# Escorna_CPU_2_01.net
KiCad netlist of a schematic drawn in EAGLE
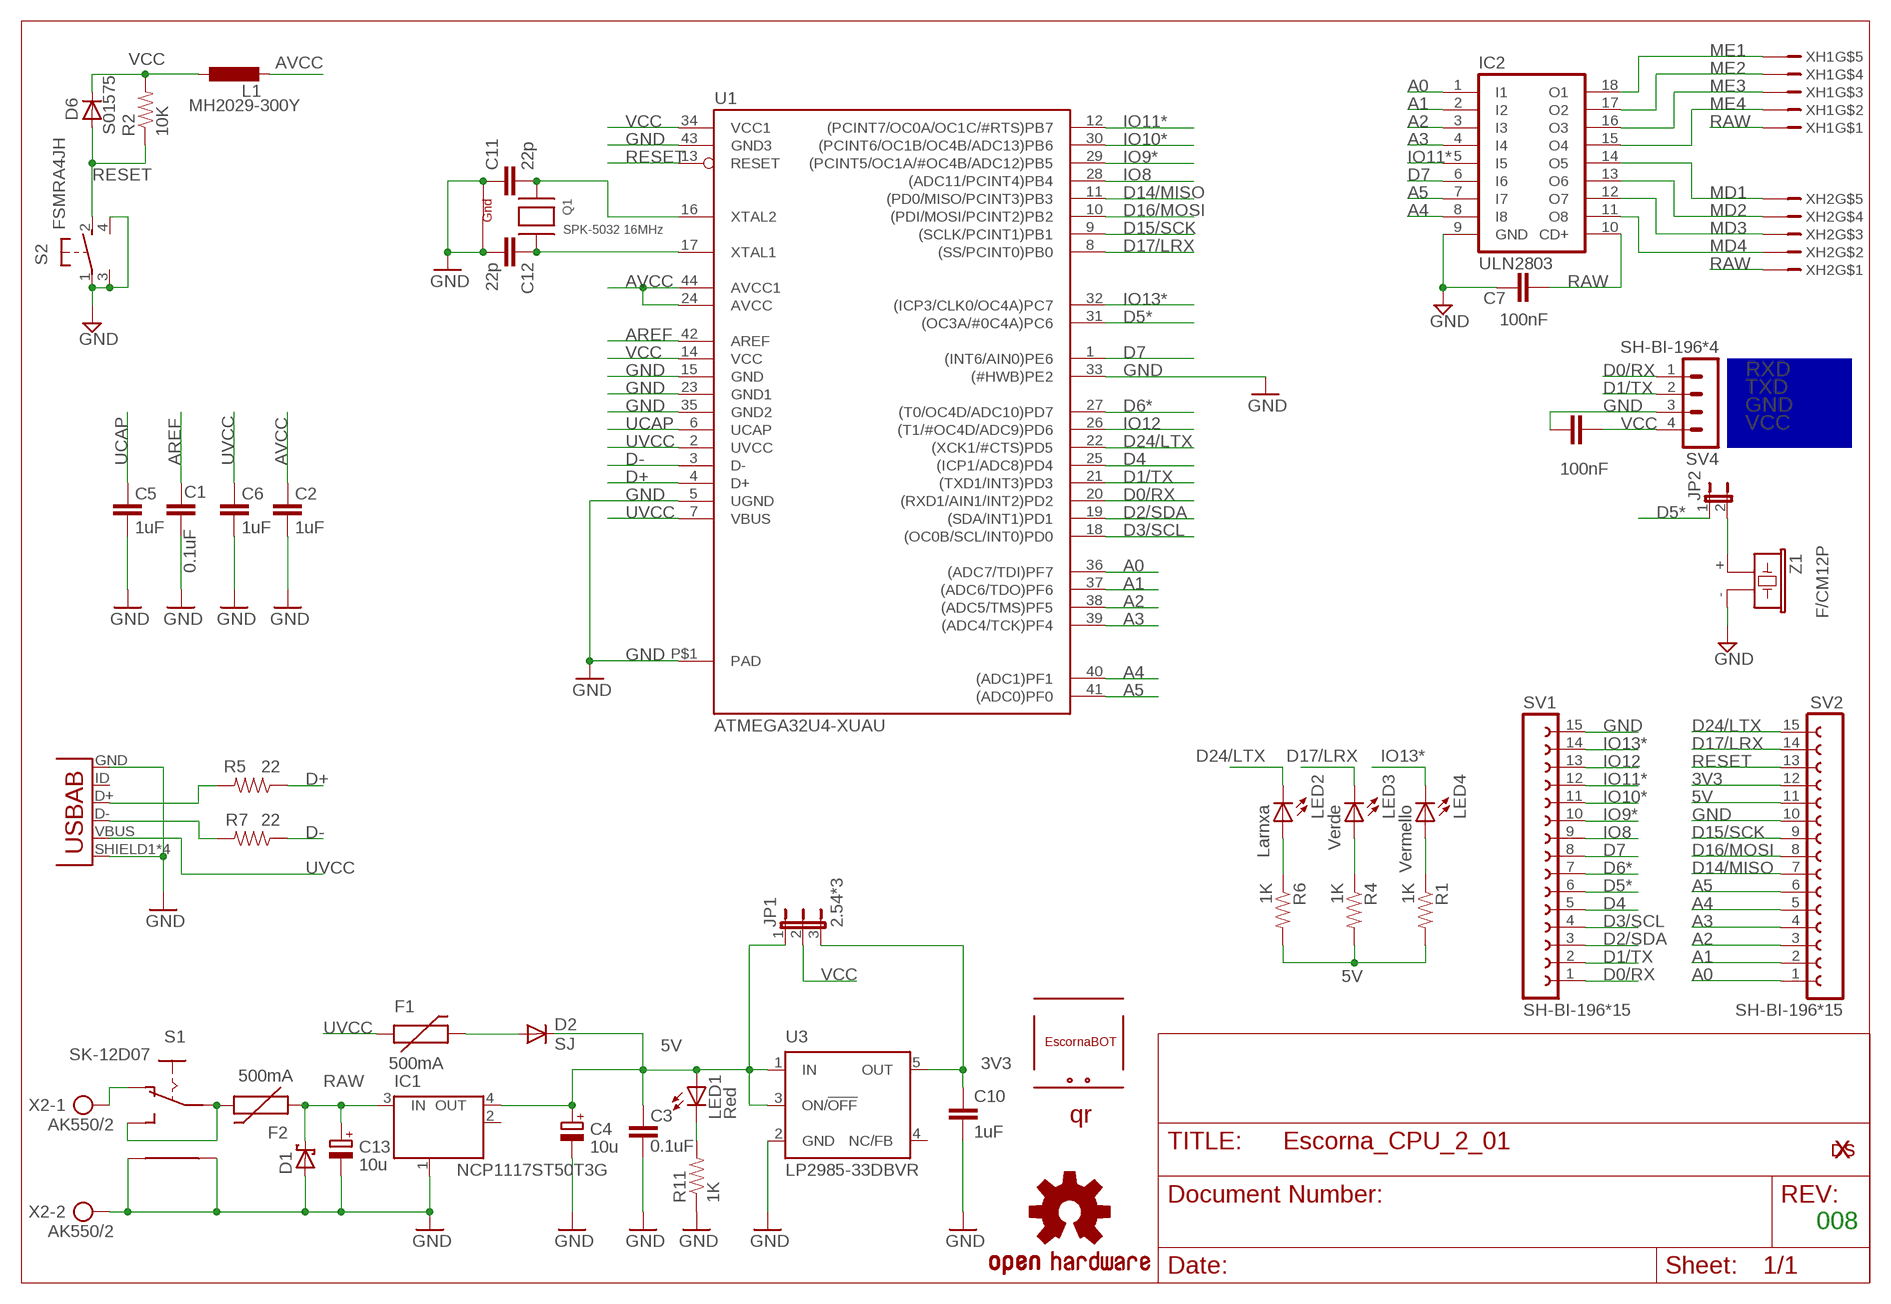
[diagram p0: schematic, sheet 1]

(export (version "E")
  (design (tool "Eeschema 10.0.6"))
  (components
    (comp (ref "C1")
      (value "0.1uF")
      (footprint "eagle-import:0603-CAP")
      (libsource (lib "eagle-import") (part "CAP0603-CAP"))
    )
    (comp (ref "C2")
      (value "1uF")
      (footprint "eagle-import:0603-CAP")
      (libsource (lib "eagle-import") (part "CAP0603-CAP"))
    )
    (comp (ref "C3")
      (value "0.1uF")
      (footprint "eagle-import:0603-CAP")
      (libsource (lib "eagle-import") (part "CAP0603-CAP"))
    )
    (comp (ref "C4")
      (value "10u")
      (footprint "eagle-import:SMC_B")
      (libsource (lib "eagle-import") (part "CPOL-EUSMCB"))
    )
    (comp (ref "C5")
      (value "1uF")
      (footprint "eagle-import:0603-CAP")
      (libsource (lib "eagle-import") (part "CAP0603-CAP"))
    )
    (comp (ref "C6")
      (value "1uF")
      (footprint "eagle-import:0603-CAP")
      (libsource (lib "eagle-import") (part "CAP0603-CAP"))
    )
    (comp (ref "C7")
      (value "100nF")
      (footprint "eagle-import:C0603K")
      (libsource (lib "eagle-import") (part "rcl_C-EUC0603K"))
    )
    (comp (ref "C8")
      (value "100nF")
      (footprint "eagle-import:C0603K")
      (libsource (lib "eagle-import") (part "rcl_C-EUC0603K"))
    )
    (comp (ref "C10")
      (value "1uF")
      (footprint "eagle-import:0603-CAP")
      (libsource (lib "eagle-import") (part "CAP0603-CAP"))
    )
    (comp (ref "C11")
      (value "22p")
      (footprint "eagle-import:C0603-ROUND")
      (libsource (lib "eagle-import") (part "C-EUC0603"))
    )
    (comp (ref "C12")
      (value "22p")
      (footprint "eagle-import:C0603-ROUND")
      (libsource (lib "eagle-import") (part "C-EUC0603"))
    )
    (comp (ref "C13")
      (value "10u")
      (footprint "eagle-import:SMC_B")
      (libsource (lib "eagle-import") (part "CPOL-EUSMCB"))
    )
    (comp (ref "D1")
      (value "SCHOTTKY-DIODESMA")
      (footprint "eagle-import:SMA")
      (libsource (lib "eagle-import") (part "SCHOTTKY-DIODESMA"))
    )
    (comp (ref "D2")
      (value "SJ")
      (footprint "eagle-import:SOD-323")
      (libsource (lib "eagle-import") (part "DIODESOD"))
    )
    (comp (ref "D6")
      (value "S01575")
      (footprint "eagle-import:SOD-323")
      (libsource (lib "eagle-import") (part "DIODESOD"))
    )
    (comp (ref "F1")
      (value "500mA")
      (footprint "eagle-import:PTC-1206")
      (libsource (lib "eagle-import") (part "PTCSMD"))
    )
    (comp (ref "F2")
      (value "500mA")
      (footprint "eagle-import:PTC-1206")
      (libsource (lib "eagle-import") (part "PTCSMD"))
    )
    (comp (ref "IC1")
      (value "NCP1117ST50T3G")
      (footprint "eagle-import:SOT223")
      (libsource (lib "eagle-import") (part "MC33269ST-3.3T3"))
    )
    (comp (ref "IC2")
      (value "ULN2803")
      (footprint "eagle-import:DIL18")
      (libsource (lib "eagle-import") (part "ULN2803A{dblquote}"))
    )
    (comp (ref "JP1")
      (value "2.54*3")
      (footprint "eagle-import:JP2")
      (libsource (lib "eagle-import") (part "JP2E"))
    )
    (comp (ref "JP2")
      (value "JP1E")
      (footprint "eagle-import:JP1")
      (libsource (lib "eagle-import") (part "JP1E"))
    )
    (comp (ref "L1")
      (value "MH2029-300Y")
      (footprint "eagle-import:L2012C")
      (libsource (lib "eagle-import") (part "L-EUL2012C"))
    )
    (comp (ref "LED1")
      (value "Red")
      (footprint "eagle-import:LED-0603")
      (libsource (lib "eagle-import") (part "LED0603"))
    )
    (comp (ref "LED2")
      (value "Larnxa")
      (footprint "eagle-import:LED-0603")
      (libsource (lib "eagle-import") (part "LED0603"))
    )
    (comp (ref "LED3")
      (value "Verde")
      (footprint "eagle-import:LED-0603")
      (libsource (lib "eagle-import") (part "LED0603"))
    )
    (comp (ref "LED4")
      (value "Vermello")
      (footprint "eagle-import:LED-0603")
      (libsource (lib "eagle-import") (part "LED0603"))
    )
    (comp (ref "LOGO1")
      (value "OSHW-LOGOS")
      (footprint "eagle-import:OSHW-LOGO-S")
      (libsource (lib "eagle-import") (part "OSHW-LOGOS"))
    )
    (comp (ref "Q1")
      (value "SPK-5032 16MHz")
      (footprint "eagle-import:NX3225")
      (libsource (lib "eagle-import") (part "XTAL-4-3225"))
    )
    (comp (ref "R1")
      (value "1K")
      (footprint "eagle-import:0603-RES")
      (libsource (lib "eagle-import") (part "RESISTOR0603-RES"))
    )
    (comp (ref "R2")
      (value "10K")
      (footprint "eagle-import:0603-RES")
      (libsource (lib "eagle-import") (part "RESISTOR0603-RES"))
    )
    (comp (ref "R4")
      (value "1K")
      (footprint "eagle-import:0603-RES")
      (libsource (lib "eagle-import") (part "RESISTOR0603-RES"))
    )
    (comp (ref "R5")
      (value "22")
      (footprint "eagle-import:0603-RES")
      (libsource (lib "eagle-import") (part "RESISTOR0603-RES"))
    )
    (comp (ref "R6")
      (value "1K")
      (footprint "eagle-import:0603-RES")
      (libsource (lib "eagle-import") (part "RESISTOR0603-RES"))
    )
    (comp (ref "R7")
      (value "22")
      (footprint "eagle-import:0603-RES")
      (libsource (lib "eagle-import") (part "RESISTOR0603-RES"))
    )
    (comp (ref "R11")
      (value "1K")
      (footprint "eagle-import:0603-RES")
      (libsource (lib "eagle-import") (part "RESISTOR0603-RES"))
    )
    (comp (ref "S1")
      (value "SK-12D07")
      (footprint "eagle-import:SK-12D07")
      (libsource (lib "eagle-import") (part "SK12F14D"))
    )
    (comp (ref "S2")
      (value "FSMRA4JH")
      (footprint "eagle-import:B3F-31XX")
      (fields (field (name "MPN") "B3F-3100"))
      (libsource (lib "eagle-import") (part "31-XX"))
    )
    (comp (ref "SV1")
      (value "SH-BI-196*15")
      (footprint "eagle-import:FE15")
      (libsource (lib "eagle-import") (part "FE15-1"))
    )
    (comp (ref "SV2")
      (value "SH-BI-196*15")
      (footprint "eagle-import:FE15")
      (libsource (lib "eagle-import") (part "FE15-1"))
    )
    (comp (ref "SV4")
      (value "SH-BI-196*4")
      (footprint "eagle-import:MA04-1")
      (libsource (lib "eagle-import") (part "MA04-1"))
    )
    (comp (ref "U$2")
      (value "XDESIG")
      (footprint "eagle-import:XDESIG_CU_2")
      (libsource (lib "eagle-import") (part "XDESIG"))
    )
    (comp (ref "U$3")
      (value "ESCORNABOT")
      (footprint "eagle-import:ESCORNA_PEQUE")
      (libsource (lib "eagle-import") (part "ESCORNABOT"))
    )
    (comp (ref "U$5")
      (value "XDESIG21")
      (footprint "eagle-import:XDESIG")
      (libsource (lib "eagle-import") (part "XDESIG21"))
    )
    (comp (ref "U$6")
      (value "QR25")
      (footprint "eagle-import:ESCORNA_QR25")
      (libsource (lib "eagle-import") (part "QR25"))
    )
    (comp (ref "U1")
      (value "ATMEGA32U4-XUAU")
      (footprint "eagle-import:TQFP44-PAD")
      (libsource (lib "eagle-import") (part "ATMEGA32U4-XUAU"))
    )
    (comp (ref "U2")
      (value "MICRO USB")
      (footprint "eagle-import:USB-AB-MICRO-SMD")
      (libsource (lib "eagle-import") (part "USB-AB"))
    )
    (comp (ref "U3")
      (value "LP2985-33DBVR")
      (footprint "eagle-import:SOT23-DBV")
      (libsource (lib "eagle-import") (part "LP2985-XXDBVR33"))
    )
    (comp (ref "X2")
      (value "AK550/2")
      (footprint "eagle-import:AK550_2")
      (libsource (lib "eagle-import") (part "AK550/2"))
    )
    (comp (ref "XH1")
      (value "XH2.54-5P")
      (footprint "eagle-import:B5B-XH-A")
      (libsource (lib "eagle-import") (part "B5B-XH-A"))
    )
    (comp (ref "XH2")
      (value "XH2.54-5P")
      (footprint "eagle-import:B5B-XH-A")
      (libsource (lib "eagle-import") (part "B5B-XH-A"))
    )
    (comp (ref "Z1")
      (value "F/CM12P")
      (footprint "eagle-import:F_CM12P")
      (libsource (lib "eagle-import") (part "F/CM12P"))
    )
  )
  (nets
    (net (code "1") (name "/3V3") (class "Default")
      (node (ref "C10") (pin "1") (pinfunction "1_1") (pintype "passive"))
      (node (ref "JP1") (pin "3") (pinfunction "3_3") (pintype "passive"))
      (node (ref "SV2") (pin "12") (pinfunction "12_12") (pintype "passive"))
      (node (ref "U3") (pin "5") (pinfunction "OUT_5") (pintype "passive"))
    )
    (net (code "2") (name "/5V") (class "Default")
      (node (ref "C3") (pin "2") (pinfunction "2_2") (pintype "passive"))
      (node (ref "C4") (pin "+") (pinfunction "+_+") (pintype "passive"))
      (node (ref "D2") (pin "1") (pinfunction "C_1") (pintype "passive"))
      (node (ref "IC1") (pin "4") (pinfunction "OUT_4") (pintype "passive"))
      (node (ref "JP1") (pin "1") (pinfunction "1_1") (pintype "passive"))
      (node (ref "LED1") (pin "A") (pinfunction "A_A") (pintype "passive"))
      (node (ref "R1") (pin "2") (pinfunction "2_2") (pintype "passive"))
      (node (ref "R4") (pin "2") (pinfunction "2_2") (pintype "passive"))
      (node (ref "R6") (pin "2") (pinfunction "2_2") (pintype "passive"))
      (node (ref "SV2") (pin "11") (pinfunction "11_11") (pintype "passive"))
      (node (ref "U3") (pin "1") (pinfunction "IN_1") (pintype "input"))
      (node (ref "U3") (pin "3") (pinfunction "ON/~{OFF}_3") (pintype "input"))
    )
    (net (code "3") (name "/A0") (class "Default")
      (node (ref "IC2") (pin "1") (pinfunction "I1_1") (pintype "input"))
      (node (ref "SV2") (pin "1") (pinfunction "1_1") (pintype "passive"))
      (node (ref "U1") (pin "36") (pinfunction "(ADC7/TDI)PF7_36") (pintype "bidirectional"))
    )
    (net (code "4") (name "/A1") (class "Default")
      (node (ref "IC2") (pin "2") (pinfunction "I2_2") (pintype "input"))
      (node (ref "SV2") (pin "2") (pinfunction "2_2") (pintype "passive"))
      (node (ref "U1") (pin "37") (pinfunction "(ADC6/TDO)PF6_37") (pintype "bidirectional"))
    )
    (net (code "5") (name "/A2") (class "Default")
      (node (ref "IC2") (pin "3") (pinfunction "I3_3") (pintype "input"))
      (node (ref "SV2") (pin "3") (pinfunction "3_3") (pintype "passive"))
      (node (ref "U1") (pin "38") (pinfunction "(ADC5/TMS)PF5_38") (pintype "bidirectional"))
    )
    (net (code "6") (name "/A3") (class "Default")
      (node (ref "IC2") (pin "4") (pinfunction "I4_4") (pintype "input"))
      (node (ref "SV2") (pin "4") (pinfunction "4_4") (pintype "passive"))
      (node (ref "U1") (pin "39") (pinfunction "(ADC4/TCK)PF4_39") (pintype "bidirectional"))
    )
    (net (code "7") (name "/A4") (class "Default")
      (node (ref "IC2") (pin "8") (pinfunction "I8_8") (pintype "input"))
      (node (ref "SV2") (pin "5") (pinfunction "5_5") (pintype "passive"))
      (node (ref "U1") (pin "40") (pinfunction "(ADC1)PF1_40") (pintype "bidirectional"))
    )
    (net (code "8") (name "/A5") (class "Default")
      (node (ref "IC2") (pin "7") (pinfunction "I7_7") (pintype "input"))
      (node (ref "SV2") (pin "6") (pinfunction "6_6") (pintype "passive"))
      (node (ref "U1") (pin "41") (pinfunction "(ADC0)PF0_41") (pintype "bidirectional"))
    )
    (net (code "9") (name "/AREF") (class "Default")
      (node (ref "C1") (pin "2") (pinfunction "2_2") (pintype "passive"))
      (node (ref "U1") (pin "42") (pinfunction "AREF_42") (pintype "power_in"))
    )
    (net (code "10") (name "/AVCC") (class "Default")
      (node (ref "C2") (pin "2") (pinfunction "2_2") (pintype "passive"))
      (node (ref "L1") (pin "2") (pinfunction "2_2") (pintype "passive"))
      (node (ref "U1") (pin "24") (pinfunction "AVCC_24") (pintype "power_in"))
      (node (ref "U1") (pin "44") (pinfunction "AVCC1_44") (pintype "power_in"))
    )
    (net (code "11") (name "/D+") (class "Default")
      (node (ref "R5") (pin "1") (pinfunction "1_1") (pintype "passive"))
      (node (ref "U1") (pin "4") (pinfunction "D+_4") (pintype "bidirectional"))
    )
    (net (code "12") (name "/D-") (class "Default")
      (node (ref "R7") (pin "1") (pinfunction "1_1") (pintype "passive"))
      (node (ref "U1") (pin "3") (pinfunction "D-_3") (pintype "bidirectional"))
    )
    (net (code "13") (name "/D0{slash}RX") (class "Default")
      (node (ref "SV1") (pin "1") (pinfunction "1_1") (pintype "passive"))
      (node (ref "SV4") (pin "1") (pinfunction "1_1") (pintype "passive"))
      (node (ref "U1") (pin "20") (pinfunction "(RXD1/AIN1/INT2)PD2_20") (pintype "bidirectional"))
    )
    (net (code "14") (name "/D1{slash}TX") (class "Default")
      (node (ref "SV1") (pin "2") (pinfunction "2_2") (pintype "passive"))
      (node (ref "SV4") (pin "2") (pinfunction "2_2") (pintype "passive"))
      (node (ref "U1") (pin "21") (pinfunction "(TXD1/INT3)PD3_21") (pintype "bidirectional"))
    )
    (net (code "15") (name "/D2{slash}SDA") (class "Default")
      (node (ref "SV1") (pin "3") (pinfunction "3_3") (pintype "passive"))
      (node (ref "U1") (pin "19") (pinfunction "(SDA/INT1)PD1_19") (pintype "bidirectional"))
    )
    (net (code "16") (name "/D3{slash}SCL") (class "Default")
      (node (ref "SV1") (pin "4") (pinfunction "4_4") (pintype "passive"))
      (node (ref "U1") (pin "18") (pinfunction "(OC0B/SCL/INT0)PD0_18") (pintype "bidirectional"))
    )
    (net (code "17") (name "/D4") (class "Default")
      (node (ref "SV1") (pin "5") (pinfunction "5_5") (pintype "passive"))
      (node (ref "U1") (pin "25") (pinfunction "(ICP1/ADC8)PD4_25") (pintype "bidirectional"))
    )
    (net (code "18") (name "/D5*") (class "Default")
      (node (ref "JP2") (pin "1") (pinfunction "1_1") (pintype "passive"))
      (node (ref "SV1") (pin "6") (pinfunction "6_6") (pintype "passive"))
      (node (ref "U1") (pin "31") (pinfunction "(OC3A/#0C4A)PC6_31") (pintype "bidirectional"))
    )
    (net (code "19") (name "/D6*") (class "Default")
      (node (ref "SV1") (pin "7") (pinfunction "7_7") (pintype "passive"))
      (node (ref "U1") (pin "27") (pinfunction "(T0/OC4D/ADC10)PD7_27") (pintype "bidirectional"))
    )
    (net (code "20") (name "/D7") (class "Default")
      (node (ref "IC2") (pin "6") (pinfunction "I6_6") (pintype "input"))
      (node (ref "SV1") (pin "8") (pinfunction "8_8") (pintype "passive"))
      (node (ref "U1") (pin "1") (pinfunction "(INT6/AIN0)PE6_1") (pintype "bidirectional"))
    )
    (net (code "21") (name "/D14{slash}MISO") (class "Default")
      (node (ref "SV2") (pin "7") (pinfunction "7_7") (pintype "passive"))
      (node (ref "U1") (pin "11") (pinfunction "(PD0/MISO/PCINT3)PB3_11") (pintype "bidirectional"))
    )
    (net (code "22") (name "/D15{slash}SCK") (class "Default")
      (node (ref "SV2") (pin "9") (pinfunction "9_9") (pintype "passive"))
      (node (ref "U1") (pin "9") (pinfunction "(SCLK/PCINT1)PB1_9") (pintype "bidirectional"))
    )
    (net (code "23") (name "/D16{slash}MOSI") (class "Default")
      (node (ref "SV2") (pin "8") (pinfunction "8_8") (pintype "passive"))
      (node (ref "U1") (pin "10") (pinfunction "(PDI/MOSI/PCINT2)PB2_10") (pintype "bidirectional"))
    )
    (net (code "24") (name "/D17{slash}LRX") (class "Default")
      (node (ref "LED3") (pin "C") (pinfunction "C_C") (pintype "passive"))
      (node (ref "SV2") (pin "14") (pinfunction "14_14") (pintype "passive"))
      (node (ref "U1") (pin "8") (pinfunction "(SS/PCINT0)PB0_8") (pintype "bidirectional"))
    )
    (net (code "25") (name "/D24{slash}LTX") (class "Default")
      (node (ref "LED2") (pin "C") (pinfunction "C_C") (pintype "passive"))
      (node (ref "SV2") (pin "15") (pinfunction "15_15") (pintype "passive"))
      (node (ref "U1") (pin "22") (pinfunction "(XCK1/#CTS)PD5_22") (pintype "bidirectional"))
    )
    (net (code "26") (name "/IO8") (class "Default")
      (node (ref "SV1") (pin "9") (pinfunction "9_9") (pintype "passive"))
      (node (ref "U1") (pin "28") (pinfunction "(ADC11/PCINT4)PB4_28") (pintype "bidirectional"))
    )
    (net (code "27") (name "/IO9*") (class "Default")
      (node (ref "SV1") (pin "10") (pinfunction "10_10") (pintype "passive"))
      (node (ref "U1") (pin "29") (pinfunction "(PCINT5/OC1A/#OC4B/ADC12)PB5_29") (pintype "bidirectional"))
    )
    (net (code "28") (name "/IO10*") (class "Default")
      (node (ref "SV1") (pin "11") (pinfunction "11_11") (pintype "passive"))
      (node (ref "U1") (pin "30") (pinfunction "(PCINT6/OC1B/OC4B/ADC13)PB6_30") (pintype "bidirectional"))
    )
    (net (code "29") (name "/IO11*") (class "Default")
      (node (ref "IC2") (pin "5") (pinfunction "I5_5") (pintype "input"))
      (node (ref "SV1") (pin "12") (pinfunction "12_12") (pintype "passive"))
      (node (ref "U1") (pin "12") (pinfunction "(PCINT7/OC0A/OC1C/#RTS)PB7_12") (pintype "bidirectional"))
    )
    (net (code "30") (name "/IO12") (class "Default")
      (node (ref "SV1") (pin "13") (pinfunction "13_13") (pintype "passive"))
      (node (ref "U1") (pin "26") (pinfunction "(T1/#OC4D/ADC9)PD6_26") (pintype "bidirectional"))
    )
    (net (code "31") (name "/IO13*") (class "Default")
      (node (ref "LED4") (pin "C") (pinfunction "C_C") (pintype "passive"))
      (node (ref "SV1") (pin "14") (pinfunction "14_14") (pintype "passive"))
      (node (ref "U1") (pin "32") (pinfunction "(ICP3/CLK0/OC4A)PC7_32") (pintype "bidirectional"))
    )
    (net (code "32") (name "/MD1") (class "Default")
      (node (ref "IC2") (pin "14") (pinfunction "O5_14") (pintype "open_collector"))
      (node (ref "XH2") (pin "P$5") (pinfunction "1_P$5") (pintype "passive"))
    )
    (net (code "33") (name "/MD2") (class "Default")
      (node (ref "IC2") (pin "13") (pinfunction "O6_13") (pintype "open_collector"))
      (node (ref "XH2") (pin "P$4") (pinfunction "1_P$4") (pintype "passive"))
    )
    (net (code "34") (name "/MD3") (class "Default")
      (node (ref "IC2") (pin "12") (pinfunction "O7_12") (pintype "open_collector"))
      (node (ref "XH2") (pin "P$3") (pinfunction "1_P$3") (pintype "passive"))
    )
    (net (code "35") (name "/MD4") (class "Default")
      (node (ref "IC2") (pin "11") (pinfunction "O8_11") (pintype "open_collector"))
      (node (ref "XH2") (pin "P$2") (pinfunction "1_P$2") (pintype "passive"))
    )
    (net (code "36") (name "/ME1") (class "Default")
      (node (ref "IC2") (pin "18") (pinfunction "O1_18") (pintype "open_collector"))
      (node (ref "XH1") (pin "P$5") (pinfunction "1_P$5") (pintype "passive"))
    )
    (net (code "37") (name "/ME2") (class "Default")
      (node (ref "IC2") (pin "17") (pinfunction "O2_17") (pintype "open_collector"))
      (node (ref "XH1") (pin "P$4") (pinfunction "1_P$4") (pintype "passive"))
    )
    (net (code "38") (name "/ME3") (class "Default")
      (node (ref "IC2") (pin "16") (pinfunction "O3_16") (pintype "open_collector"))
      (node (ref "XH1") (pin "P$3") (pinfunction "1_P$3") (pintype "passive"))
    )
    (net (code "39") (name "/ME4") (class "Default")
      (node (ref "IC2") (pin "15") (pinfunction "O4_15") (pintype "open_collector"))
      (node (ref "XH1") (pin "P$2") (pinfunction "1_P$2") (pintype "passive"))
    )
    (net (code "40") (name "/RAW") (class "Default")
      (node (ref "C13") (pin "+") (pinfunction "+_+") (pintype "passive"))
      (node (ref "C7") (pin "2") (pinfunction "2_2") (pintype "passive"))
      (node (ref "D1") (pin "C") (pinfunction "C_C") (pintype "passive"))
      (node (ref "F2") (pin "1") (pinfunction "1_1") (pintype "bidirectional"))
      (node (ref "IC1") (pin "3") (pinfunction "IN_3") (pintype "input"))
      (node (ref "IC2") (pin "10") (pinfunction "CD+_10") (pintype "passive"))
      (node (ref "XH1") (pin "P$1") (pinfunction "1_P$1") (pintype "passive"))
      (node (ref "XH2") (pin "P$1") (pinfunction "1_P$1") (pintype "passive"))
    )
    (net (code "41") (name "/RESET") (class "Default")
      (node (ref "D6") (pin "2") (pinfunction "A_2") (pintype "passive"))
      (node (ref "R2") (pin "1") (pinfunction "1_1") (pintype "passive"))
      (node (ref "S2") (pin "2") (pinfunction "S_2") (pintype "passive"))
      (node (ref "SV2") (pin "13") (pinfunction "13_13") (pintype "passive"))
      (node (ref "U1") (pin "13") (pinfunction "RESET_13") (pintype "input"))
    )
    (net (code "42") (name "/UCAP") (class "Default")
      (node (ref "C5") (pin "2") (pinfunction "2_2") (pintype "passive"))
      (node (ref "U1") (pin "6") (pinfunction "UCAP_6") (pintype "passive"))
    )
    (net (code "43") (name "/UVCC") (class "Default")
      (node (ref "C6") (pin "2") (pinfunction "2_2") (pintype "passive"))
      (node (ref "F1") (pin "1") (pinfunction "1_1") (pintype "bidirectional"))
      (node (ref "U1") (pin "2") (pinfunction "UVCC_2") (pintype "power_in"))
      (node (ref "U1") (pin "7") (pinfunction "VBUS_7") (pintype "input"))
      (node (ref "U2") (pin "VBUS") (pinfunction "VBUS_VBUS") (pintype "bidirectional"))
    )
    (net (code "44") (name "/VCC") (class "Default")
      (node (ref "C8") (pin "2") (pinfunction "2_2") (pintype "passive"))
      (node (ref "D6") (pin "1") (pinfunction "C_1") (pintype "passive"))
      (node (ref "JP1") (pin "2") (pinfunction "2_2") (pintype "passive"))
      (node (ref "L1") (pin "1") (pinfunction "1_1") (pintype "passive"))
      (node (ref "R2") (pin "2") (pinfunction "2_2") (pintype "passive"))
      (node (ref "SV4") (pin "4") (pinfunction "4_4") (pintype "passive"))
      (node (ref "U1") (pin "14") (pinfunction "VCC_14") (pintype "power_in"))
      (node (ref "U1") (pin "34") (pinfunction "VCC1_34") (pintype "power_in"))
    )
    (net (code "45") (name "GND") (class "Default")
      (node (ref "C1") (pin "1") (pinfunction "1_1") (pintype "passive"))
      (node (ref "C10") (pin "2") (pinfunction "2_2") (pintype "passive"))
      (node (ref "C11") (pin "1") (pinfunction "1_1") (pintype "passive"))
      (node (ref "C12") (pin "2") (pinfunction "2_2") (pintype "passive"))
      (node (ref "C13") (pin "-") (pinfunction "-_-") (pintype "passive"))
      (node (ref "C2") (pin "1") (pinfunction "1_1") (pintype "passive"))
      (node (ref "C3") (pin "1") (pinfunction "1_1") (pintype "passive"))
      (node (ref "C4") (pin "-") (pinfunction "-_-") (pintype "passive"))
      (node (ref "C5") (pin "1") (pinfunction "1_1") (pintype "passive"))
      (node (ref "C6") (pin "1") (pinfunction "1_1") (pintype "passive"))
      (node (ref "C7") (pin "1") (pinfunction "1_1") (pintype "passive"))
      (node (ref "C8") (pin "1") (pinfunction "1_1") (pintype "passive"))
      (node (ref "D1") (pin "A") (pinfunction "A_A") (pintype "passive"))
      (node (ref "IC1") (pin "1") (pinfunction "GND/ADJ_1") (pintype "input"))
      (node (ref "IC2") (pin "9") (pinfunction "GND_9") (pintype "power_in"))
      (node (ref "Q1") (pin "2") (pinfunction "G2_2") (pintype "power_in"))
      (node (ref "Q1") (pin "4") (pinfunction "G1_4") (pintype "power_in"))
      (node (ref "R11") (pin "1") (pinfunction "1_1") (pintype "passive"))
      (node (ref "S1") (pin "P$4") (pinfunction "P$1_P$4") (pintype "passive"))
      (node (ref "S1") (pin "P$5") (pinfunction "P$2_P$5") (pintype "bidirectional"))
      (node (ref "S2") (pin "1") (pinfunction "P_1") (pintype "passive"))
      (node (ref "S2") (pin "3") (pinfunction "CH2_3") (pintype "bidirectional"))
      (node (ref "S2") (pin "4") (pinfunction "CH1_4") (pintype "bidirectional"))
      (node (ref "SV1") (pin "15") (pinfunction "15_15") (pintype "passive"))
      (node (ref "SV2") (pin "10") (pinfunction "10_10") (pintype "passive"))
      (node (ref "SV4") (pin "3") (pinfunction "3_3") (pintype "passive"))
      (node (ref "U1") (pin "15") (pinfunction "GND_15") (pintype "power_in"))
      (node (ref "U1") (pin "23") (pinfunction "GND1_23") (pintype "power_in"))
      (node (ref "U1") (pin "33") (pinfunction "(#HWB)PE2_33") (pintype "bidirectional"))
      (node (ref "U1") (pin "35") (pinfunction "GND2_35") (pintype "power_in"))
      (node (ref "U1") (pin "43") (pinfunction "GND3_43") (pintype "power_in"))
      (node (ref "U1") (pin "5") (pinfunction "UGND_5") (pintype "power_in"))
      (node (ref "U1") (pin "P$1") (pinfunction "PAD_P$1") (pintype "power_in"))
      (node (ref "U2") (pin "GND") (pinfunction "GND_GND") (pintype "bidirectional"))
      (node (ref "U2") (pin "SHIELD1") (pinfunction "SHIELD_SHIELD1") (pintype "bidirectional"))
      (node (ref "U2") (pin "SHIELD2") (pinfunction "SHIELD_SHIELD2") (pintype "bidirectional"))
      (node (ref "U2") (pin "SHIELD3") (pinfunction "SHIELD_SHIELD3") (pintype "bidirectional"))
      (node (ref "U2") (pin "SHIELD4") (pinfunction "SHIELD_SHIELD4") (pintype "bidirectional"))
      (node (ref "U3") (pin "2") (pinfunction "GND_2") (pintype "power_in"))
      (node (ref "X2") (pin "2") (pinfunction "KL_2") (pintype "passive"))
      (node (ref "Z1") (pin "-") (pinfunction "2_-") (pintype "passive"))
    )
    (net (code "46") (name "Net-(D2-A)") (class "Default")
      (node (ref "D2") (pin "2") (pinfunction "A_2") (pintype "passive"))
      (node (ref "F1") (pin "2") (pinfunction "2_2") (pintype "bidirectional"))
    )
    (net (code "47") (name "Net-(LED1-PadC)") (class "Default")
      (node (ref "LED1") (pin "C") (pinfunction "C_C") (pintype "passive"))
      (node (ref "R11") (pin "2") (pinfunction "2_2") (pintype "passive"))
    )
    (net (code "48") (name "Net-(LED2-PadA)") (class "Default")
      (node (ref "LED2") (pin "A") (pinfunction "A_A") (pintype "passive"))
      (node (ref "R6") (pin "1") (pinfunction "1_1") (pintype "passive"))
    )
    (net (code "49") (name "Net-(LED3-PadA)") (class "Default")
      (node (ref "LED3") (pin "A") (pinfunction "A_A") (pintype "passive"))
      (node (ref "R4") (pin "1") (pinfunction "1_1") (pintype "passive"))
    )
    (net (code "50") (name "Net-(LED4-PadA)") (class "Default")
      (node (ref "LED4") (pin "A") (pinfunction "A_A") (pintype "passive"))
      (node (ref "R1") (pin "1") (pinfunction "1_1") (pintype "passive"))
    )
    (net (code "51") (name "Net-(Q1-X1)") (class "Default")
      (node (ref "C11") (pin "2") (pinfunction "2_2") (pintype "passive"))
      (node (ref "Q1") (pin "1") (pinfunction "X1_1") (pintype "bidirectional"))
      (node (ref "U1") (pin "16") (pinfunction "XTAL2_16") (pintype "bidirectional"))
    )
    (net (code "52") (name "Net-(Q1-X2)") (class "Default")
      (node (ref "C12") (pin "1") (pinfunction "1_1") (pintype "passive"))
      (node (ref "Q1") (pin "3") (pinfunction "X2_3") (pintype "bidirectional"))
      (node (ref "U1") (pin "17") (pinfunction "XTAL1_17") (pintype "bidirectional"))
    )
    (net (code "53") (name "Net-(R5-Pad2)") (class "Default")
      (node (ref "R5") (pin "2") (pinfunction "2_2") (pintype "passive"))
      (node (ref "U2") (pin "D+") (pinfunction "D+_D+") (pintype "bidirectional"))
    )
    (net (code "54") (name "Net-(R7-Pad2)") (class "Default")
      (node (ref "R7") (pin "2") (pinfunction "2_2") (pintype "passive"))
      (node (ref "U2") (pin "D-") (pinfunction "D-_D-") (pintype "bidirectional"))
    )
    (net (code "55") (name "Net-(S1-O)") (class "Default")
      (node (ref "S1") (pin "P$2") (pinfunction "O_P$2") (pintype "passive"))
      (node (ref "X2") (pin "1") (pinfunction "KL_1") (pintype "passive"))
    )
    (net (code "56") (name "Net-(S1-P)") (class "Default")
      (node (ref "F2") (pin "2") (pinfunction "2_2") (pintype "bidirectional"))
      (node (ref "S1") (pin "P$1") (pinfunction "P_P$1") (pintype "passive"))
      (node (ref "S1") (pin "P$3") (pinfunction "S_P$3") (pintype "passive"))
    )
    (net (code "57") (name "Net-(Z1-1)") (class "Default")
      (node (ref "JP2") (pin "2") (pinfunction "2_2") (pintype "passive"))
      (node (ref "Z1") (pin "+") (pinfunction "1_+") (pintype "passive"))
    )
    (net (code "58") (name "unconnected-(IC1-OUT-Pad2)") (class "Default")
      (node (ref "IC1") (pin "2") (pinfunction "OUT_2") (pintype "passive"))
    )
    (net (code "59") (name "unconnected-(U2-USBID-PadID)") (class "Default")
      (node (ref "U2") (pin "ID") (pinfunction "USBID_ID") (pintype "bidirectional"))
    )
    (net (code "60") (name "unconnected-(U3-NC{slash}FB-Pad4)") (class "Default")
      (node (ref "U3") (pin "4") (pinfunction "NC/FB_4") (pintype "passive"))
    )
  )
)
